# ModemPower.net
KiCad netlist of a schematic drawn in Altium Designer
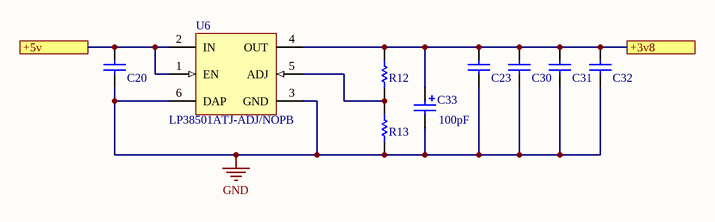
[diagram p0: ModemPower.SchDoc]

(export (version "E")
  (design (tool "Eeschema 10.0.6"))
  (components
    (comp (ref "C20")
      (value "CAP_1_9")
      (footprint "0402")
      (description "10uF 20% 16V")
      (fields (field (name "TOLERANCE") "20%") (field (name "VOLTAGE") "16V"))
      (libsource (lib "CPHComponentSource") (part "CAP_1_9"))
    )
    (comp (ref "C23")
      (value "CAP_1_6")
      (footprint "0402")
      (description "100nF 20% 16V")
      (fields (field (name "TOLERANCE") "20%") (field (name "VOLTAGE") "16V"))
      (libsource (lib "CPHComponentSource") (part "CAP_1_6"))
    )
    (comp (ref "C30")
      (value "CAP_1_7")
      (footprint "0402")
      (description "10nF 10% 50V")
      (fields (field (name "TOLERANCE") "10%") (field (name "VOLTAGE") "50V"))
      (libsource (lib "CPHComponentSource") (part "CAP_1_7"))
    )
    (comp (ref "C31")
      (value "CAP_1_8")
      (footprint "0402")
      (description "68pF 5% 50V")
      (fields (field (name "TOLERANCE") "5%") (field (name "VOLTAGE") "50V"))
      (libsource (lib "CPHComponentSource") (part "CAP_1_8"))
    )
    (comp (ref "C32")
      (value "CAP_1_18")
      (footprint "0402")
      (description "16pF 5% 50V")
      (fields (field (name "TOLERANCE") "5%") (field (name "VOLTAGE") "50V"))
      (libsource (lib "CPHComponentSource") (part "CAP_1_18"))
    )
    (comp (ref "C33")
      (value "100pF")
      (footprint "POLAR0.8")
      (description "Polarized Capacitor (Axial)")
      (fields
        (field (name "MANUFACTURER") "KEMET")
        (field (name "MANUFACTURER PART NUMBER") "T520B107M006ATE015")
        (field (name "PUBLISHER") "Altium Limited")
      )
      (libsource (lib "Miscellaneous Devices") (part "Cap Pol2"))
    )
    (comp (ref "R12")
      (value "RES_37")
      (footprint "0402")
      (description "RES 4.7K 0.1W ±5% 0603 (1608)")
      (libsource (lib "CPHComponentSource") (part "RES_37"))
    )
    (comp (ref "R13")
      (value "RES_37")
      (footprint "0402")
      (description "RES 4.7K 0.1W ±5% 0603 (1608)")
      (libsource (lib "CPHComponentSource") (part "RES_37"))
    )
    (comp (ref "U6")
      (value "LP38501ATJ-ADJ/NOPB")
      (footprint "TJ5A_N")
      (description "3A FlexCap Low Dropout Linear Regulator for 2.7V to 5.5V Inputs, 5-pin TO-263 Thin, Pb-Free")
      (fields (field (name "MANUFACTURER") "National Semiconductor"))
      (libsource (lib "National Semiconductor LDO") (part "LP38501ATJ-ADJ/NOPB"))
    )
  )
  (nets
    (net (code "1") (name "/+3v8") (class "Default")
      (node (ref "C23") (pin "2") (pinfunction "2_2") (pintype "passive"))
      (node (ref "C30") (pin "2") (pinfunction "2_2") (pintype "passive"))
      (node (ref "C31") (pin "2") (pinfunction "2_2") (pintype "passive"))
      (node (ref "C32") (pin "2") (pinfunction "2_2") (pintype "passive"))
      (node (ref "C33") (pin "1") (pinfunction "1_1") (pintype "passive"))
      (node (ref "R12") (pin "2") (pinfunction "2_2") (pintype "passive"))
      (node (ref "U6") (pin "4") (pinfunction "OUT_4") (pintype "power_in"))
    )
    (net (code "2") (name "/+5v") (class "Default")
      (node (ref "C20") (pin "2") (pinfunction "2_2") (pintype "passive"))
      (node (ref "U6") (pin "1") (pinfunction "EN_1") (pintype "input"))
      (node (ref "U6") (pin "2") (pinfunction "IN_2") (pintype "power_in"))
    )
    (net (code "3") (name "GND") (class "Default")
      (node (ref "C20") (pin "1") (pinfunction "1_1") (pintype "passive"))
      (node (ref "C23") (pin "1") (pinfunction "1_1") (pintype "passive"))
      (node (ref "C30") (pin "1") (pinfunction "1_1") (pintype "passive"))
      (node (ref "C31") (pin "1") (pinfunction "1_1") (pintype "passive"))
      (node (ref "C32") (pin "1") (pinfunction "1_1") (pintype "passive"))
      (node (ref "C33") (pin "2") (pinfunction "2_2") (pintype "passive"))
      (node (ref "R13") (pin "1") (pinfunction "1_1") (pintype "passive"))
      (node (ref "U6") (pin "3") (pinfunction "GND_3") (pintype "power_in"))
      (node (ref "U6") (pin "6") (pinfunction "DAP_6") (pintype "power_in"))
    )
    (net (code "4") (name "Net-(U6-ADJ)") (class "Default")
      (node (ref "R12") (pin "1") (pinfunction "1_1") (pintype "passive"))
      (node (ref "R13") (pin "2") (pinfunction "2_2") (pintype "passive"))
      (node (ref "U6") (pin "5") (pinfunction "ADJ_5") (pintype "input"))
    )
  )
)
